# Sheet2.net
KiCad netlist of a schematic drawn in Altium Designer
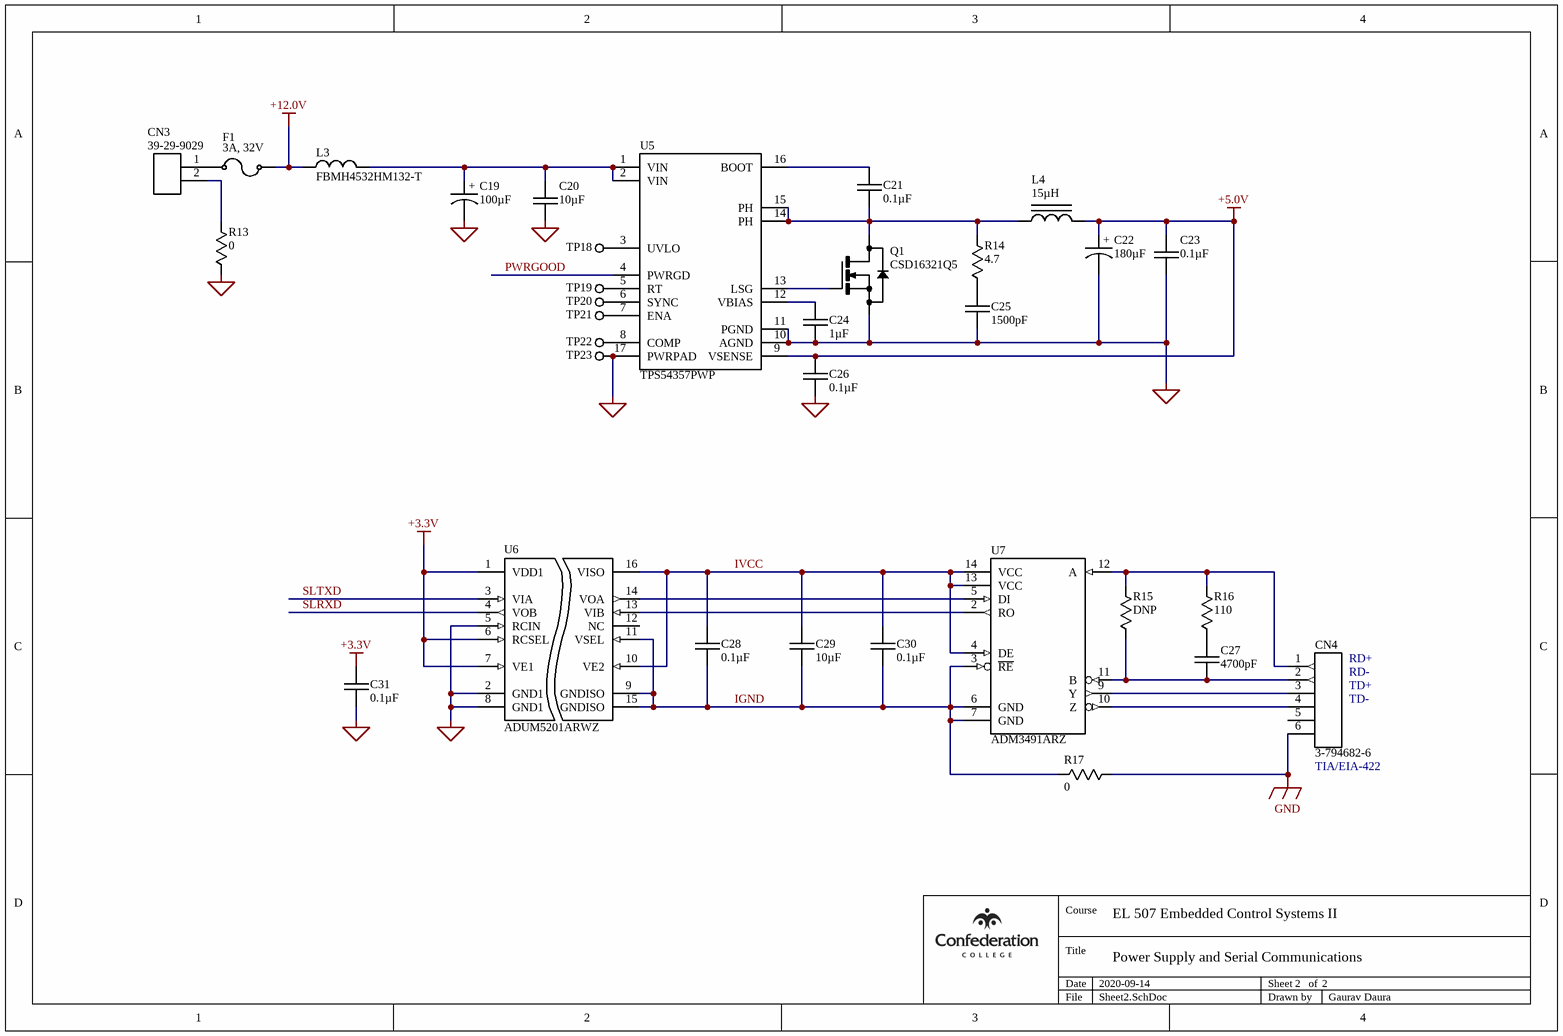
[diagram p0: Sheet2.SchDoc]

(export (version "E")
  (design (tool "Eeschema 10.0.6"))
  (components
    (comp (ref "C19")
      (value "100µF")
      (footprint "CAPAE660X770N")
      (description "100µF/25V/20% Aluminum Electrolytic Capacitor")
      (fields
        (field (name "MANUFACTURER") "Panasonic Corporation of North America")
        (field (name "PARTNUMBER") "EEE-1EA101XP")
      )
      (libsource (lib "EL507-LAB001") (part "EEE-1EA101XP"))
    )
    (comp (ref "C20")
      (value "10µF")
      (footprint "CAPC3225X250N")
      (description "10µF/50V/20% Multilayer Ceramic Chip Capacitor")
      (fields (field (name "MANUFACTURER") "Taiyo Yuden") (field (name "PARTNUMBER") "UMK325C7106MM-T"))
      (libsource (lib "EL507-LAB001") (part "UMK325C7106MM-T"))
    )
    (comp (ref "C21")
      (value "0.1µF")
      (footprint "CAPC2012X125N")
      (description "0.1µF/50V/±10% X7R Ceramic Chip Capacitor")
      (fields
        (field (name "MANUFACTURER") "Murata Manufacturing Co., Ltd.")
        (field (name "PARTNUMBER") "GRM21BR71H104KA01L")
      )
      (libsource (lib "EL507-LAB001") (part "GRM21BR71H104KA01L"))
    )
    (comp (ref "C22")
      (value "180µF")
      (footprint "CAPMP7343X190N")
      (description "180µF/6.3V/20% Low ESR Polymer Aluminum Capacitor (SP-CAP)")
      (fields
        (field (name "MANUFACTURER") "Panasonic Corporation of North America")
        (field (name "PARTNUMBER") "EEF-SE0J181R")
      )
      (libsource (lib "EL507-LAB001") (part "EEF-SE0J181R"))
    )
    (comp (ref "C23")
      (value "0.1µF")
      (footprint "CAPC2012X125N")
      (description "0.1µF/50V/±10% X7R Ceramic Chip Capacitor")
      (fields
        (field (name "MANUFACTURER") "Murata Manufacturing Co., Ltd.")
        (field (name "PARTNUMBER") "GRM21BR71H104KA01L")
      )
      (libsource (lib "EL507-LAB001") (part "GRM21BR71H104KA01L"))
    )
    (comp (ref "C24")
      (value "1µF")
      (footprint "CAPC2012X135N")
      (description "1µF/50V 10% X7R Multi-Layer Ceramic Capacitor")
      (fields
        (field (name "MANUFACTURER") "Samsung Electro-Mechanics")
        (field (name "PARTNUMBER") "CL21B105KBFNNNE")
      )
      (libsource (lib "EL507-LAB001") (part "CL21B105KBFNNNE"))
    )
    (comp (ref "C25")
      (value "1500pF")
      (footprint "CAPC2012X100N")
      (description "1500pF/250V/±10% X7R Ceramic Chip Capacitor")
      (fields
        (field (name "MANUFACTURER") "Murata Manufacturing Co., Ltd.")
        (field (name "PARTNUMBER") "GRM21AR72E152KW01D")
      )
      (libsource (lib "EL507-LAB001") (part "GRM21AR72E152KW01D"))
    )
    (comp (ref "C26")
      (value "0.1µF")
      (footprint "CAPC2012X125N")
      (description "0.1µF/50V/±10% X7R Ceramic Chip Capacitor")
      (fields
        (field (name "MANUFACTURER") "Murata Manufacturing Co., Ltd.")
        (field (name "PARTNUMBER") "GRM21BR71H104KA01L")
      )
      (libsource (lib "EL507-LAB001") (part "GRM21BR71H104KA01L"))
    )
    (comp (ref "C27")
      (value "4700pF")
      (footprint "CAPC2012X78N")
      (description "4700pF/50V/10% Ceramic Capacitor")
      (fields
        (field (name "MANUFACTURER") "Kemet Electronics Corporation")
        (field (name "PARTNUMBER") "C0805C472K5RACTU")
      )
      (libsource (lib "EL507-LAB001") (part "C0805C472K5RACTU"))
    )
    (comp (ref "C28")
      (value "0.1µF")
      (footprint "CAPC2012X125N")
      (description "0.1µF/50V/±10% X7R Ceramic Chip Capacitor")
      (fields
        (field (name "MANUFACTURER") "Murata Manufacturing Co., Ltd.")
        (field (name "PARTNUMBER") "GRM21BR71H104KA01L")
      )
      (libsource (lib "EL507-LAB001") (part "GRM21BR71H104KA01L"))
    )
    (comp (ref "C29")
      (value "10µF")
      (footprint "CAPC3225X250N")
      (description "10µF/50V/20% Multilayer Ceramic Chip Capacitor")
      (fields (field (name "MANUFACTURER") "Taiyo Yuden") (field (name "PARTNUMBER") "UMK325C7106MM-T"))
      (libsource (lib "EL507-LAB001") (part "UMK325C7106MM-T"))
    )
    (comp (ref "C30")
      (value "0.1µF")
      (footprint "CAPC2012X125N")
      (description "0.1µF/50V/±10% X7R Ceramic Chip Capacitor")
      (fields
        (field (name "MANUFACTURER") "Murata Manufacturing Co., Ltd.")
        (field (name "PARTNUMBER") "GRM21BR71H104KA01L")
      )
      (libsource (lib "EL507-LAB001") (part "GRM21BR71H104KA01L"))
    )
    (comp (ref "C31")
      (value "0.1µF")
      (footprint "CAPC2012X125N")
      (description "0.1µF/50V/±10% X7R Ceramic Chip Capacitor")
      (fields
        (field (name "MANUFACTURER") "Murata Manufacturing Co., Ltd.")
        (field (name "PARTNUMBER") "GRM21BR71H104KA01L")
      )
      (libsource (lib "EL507-LAB001") (part "GRM21BR71H104KA01L"))
    )
    (comp (ref "CN3")
      (value "39-29-9029")
      (footprint "MOLEX_39-29-9029")
      (fields (field (name "MANUFACTURER") "Molex Inc."))
      (libsource (lib "EL507-LAB001") (part "39-29-9029"))
    )
    (comp (ref "CN4")
      (value "3-794682-6")
      (footprint "TYCO_3-794682-6")
      (description "6 Circuit, Micro MATE-N-LOK 3 mm Vertical Connector")
      (fields (field (name "MANUFACTURER") "Tyco Electronics Corporation"))
      (libsource (lib "EL507-LAB001") (part "3-794682-6"))
    )
    (comp (ref "F1")
      (value "3A, 32V")
      (footprint "FUSE_0468XXX.NR")
      (description "1 A, 32 V, Slo-Blo, 468 Series Surface Mount Fuse")
      (fields (field (name "PARTNUMBER") "0468003.NR") (field (name "MANUFACTURER") "Littelfuse, Inc."))
      (libsource (lib "EL507-LAB001") (part "0468003.NR"))
    )
    (comp (ref "L3")
      (value "FBMH4532HM132-T")
      (footprint "INDC4532X350N")
      (description "Multilayer SMD Ferrite Bead, 3A, 1.3k @ 100 MHz")
      (fields (field (name "MANUFACTURER") "Taiyo Yuden"))
      (libsource (lib "EL507-LAB001") (part "FBMH4532HM132-T"))
    )
    (comp (ref "L4")
      (value "15µH")
      (footprint "IND_SRU1038-150Y")
      (description "15µH Shielded SMD Power Inductor")
      (fields (field (name "PARTNUMBER") "SRU1038-150Y") (field (name "MANUFACTURER") "Bourns, Inc."))
      (libsource (lib "EL507-LAB001") (part "SRU1038-150Y"))
    )
    (comp (ref "Q1")
      (value "CSD16321Q5")
      (footprint "TI_CSD16321Q5")
      (description "25V, 31 A, N-Channel Power MOSFET")
      (fields (field (name "MANUFACTURER") "Texas Instruments, Inc."))
      (libsource (lib "EL507-LAB001") (part "CSD16321Q5"))
    )
    (comp (ref "R13")
      (value "0")
      (footprint "RESC3216X60N")
      (description "0, 5%, 0.25W Thick Film Chip Resistor")
      (fields
        (field (name "MANUFACTURER") "Panasonic Corporation of North America")
        (field (name "PARTNUMBER") "ERJ-8GEY0R00V")
      )
      (libsource (lib "EL507-LAB001") (part "ERJ-8GEY0R00V"))
    )
    (comp (ref "R14")
      (value "4.7")
      (footprint "RESC2012X60N")
      (description "4.7, ±5%, 0.125W Thick Film Chip Resistor")
      (fields
        (field (name "MANUFACTURER") "Panasonic Corporation of North America")
        (field (name "PARTNUMBER") "ERJ-6GEYJ4R7V")
      )
      (libsource (lib "EL507-LAB001") (part "ERJ-6GEYJ4R7V"))
    )
    (comp (ref "R15")
      (value "DNP")
      (footprint "RESC2012X60N")
      (description "2012 Chip Resistor")
      (fields (field (name "MANUFACTURER") "Confederation College"))
      (libsource (lib "EL507-LAB001") (part "DNP_RESC2012X60N"))
    )
    (comp (ref "R16")
      (value "110")
      (footprint "RESC2012X60N")
      (description "110, 1%, 0.125W Precision Thick Film Chip Resistor")
      (fields
        (field (name "MANUFACTURER") "Panasonic Corporation of North America")
        (field (name "PARTNUMBER") "ERJ-6ENF1100V")
      )
      (libsource (lib "EL507-LAB001") (part "ERJ-6ENF1100V"))
    )
    (comp (ref "R17")
      (value "0")
      (footprint "RESC3216X60N")
      (description "0, 5%, 0.25W Thick Film Chip Resistor")
      (fields
        (field (name "MANUFACTURER") "Panasonic Corporation of North America")
        (field (name "PARTNUMBER") "ERJ-8GEY0R00V")
      )
      (libsource (lib "EL507-LAB001") (part "ERJ-8GEY0R00V"))
    )
    (comp (ref "TP18")
      (value "TESTPOINT100")
      (footprint "TP100")
      (description "Test Point")
      (fields (field (name "MANUFACTURER") "Confederation College"))
      (libsource (lib "EL507-LAB001") (part "TESTPOINT100"))
    )
    (comp (ref "TP19")
      (value "TESTPOINT100")
      (footprint "TP100")
      (description "Test Point")
      (fields (field (name "MANUFACTURER") "Confederation College"))
      (libsource (lib "EL507-LAB001") (part "TESTPOINT100"))
    )
    (comp (ref "TP20")
      (value "TESTPOINT100")
      (footprint "TP100")
      (description "Test Point")
      (fields (field (name "MANUFACTURER") "Confederation College"))
      (libsource (lib "EL507-LAB001") (part "TESTPOINT100"))
    )
    (comp (ref "TP21")
      (value "TESTPOINT100")
      (footprint "TP100")
      (description "Test Point")
      (fields (field (name "MANUFACTURER") "Confederation College"))
      (libsource (lib "EL507-LAB001") (part "TESTPOINT100"))
    )
    (comp (ref "TP22")
      (value "TESTPOINT100")
      (footprint "TP100")
      (description "Test Point")
      (fields (field (name "MANUFACTURER") "Confederation College"))
      (libsource (lib "EL507-LAB001") (part "TESTPOINT100"))
    )
    (comp (ref "TP23")
      (value "TESTPOINT100")
      (footprint "TP100")
      (description "Test Point")
      (fields (field (name "MANUFACTURER") "Confederation College"))
      (libsource (lib "EL507-LAB001") (part "TESTPOINT100"))
    )
    (comp (ref "U5")
      (value "TPS54357PWP")
      (footprint "SOP65P640X120-17AN")
      (description "5V, 4.5V to 20V Input, 3A Output Synchronous PWM Switcher with Integrated FET (SWIFT)")
      (fields (field (name "MANUFACTURER") "Texas Instruments, Inc."))
      (libsource (lib "EL507-LAB001") (part "TPS54357PWP"))
    )
    (comp (ref "U6")
      (value "ADUM5201ARWZ")
      (footprint "SOIC127P1030X265-16N")
      (description "1Mbps Dual Channel Digital Isolator with isoPower Integrated DC-to-DC Converter, 2.5 kV")
      (fields (field (name "MANUFACTURER") "Analog Devices, Inc."))
      (libsource (lib "EL507-LAB001") (part "ADUM5201ARWZ"))
    )
    (comp (ref "U7")
      (value "ADM3491ARZ")
      (footprint "SOIC127P600X175-14N")
      (description "3.3 V, Full Duplex, 840 uA, 20 Mbps, EIA RS-485 Transceiver")
      (fields (field (name "MANUFACTURER") "Analog Devices, Inc."))
      (libsource (lib "EL507-LAB001") (part "ADM3491ARZ"))
    )
  )
  (nets
    (net (code "1") (name "+3.3V") (class "Default")
      (node (ref "C31") (pin "1") (pinfunction "1_1") (pintype "passive"))
      (node (ref "U6") (pin "1") (pinfunction "VDD1_1") (pintype "power_in"))
      (node (ref "U6") (pin "6") (pinfunction "RCSEL_6") (pintype "input"))
      (node (ref "U6") (pin "7") (pinfunction "VE1_7") (pintype "input"))
    )
    (net (code "2") (name "+5.0V") (class "Default")
      (node (ref "C22") (pin "1") (pinfunction "1_1") (pintype "passive"))
      (node (ref "C23") (pin "1") (pinfunction "1_1") (pintype "passive"))
      (node (ref "C26") (pin "1") (pinfunction "1_1") (pintype "passive"))
      (node (ref "L4") (pin "2") (pinfunction "2_2") (pintype "passive"))
      (node (ref "U5") (pin "9") (pinfunction "VSENSE_9") (pintype "passive"))
    )
    (net (code "3") (name "+12.0V") (class "Default")
      (node (ref "F1") (pin "2") (pinfunction "2_2") (pintype "passive"))
      (node (ref "L3") (pin "1") (pinfunction "1_1") (pintype "passive"))
    )
    (net (code "4") (name "/IGND") (class "Default")
      (node (ref "C28") (pin "2") (pinfunction "2_2") (pintype "passive"))
      (node (ref "C29") (pin "2") (pinfunction "2_2") (pintype "passive"))
      (node (ref "C30") (pin "2") (pinfunction "2_2") (pintype "passive"))
      (node (ref "R17") (pin "1") (pinfunction "1_1") (pintype "passive"))
      (node (ref "U6") (pin "11") (pinfunction "VSEL_11") (pintype "input"))
      (node (ref "U6") (pin "15") (pinfunction "GNDISO_15") (pintype "power_in"))
      (node (ref "U6") (pin "9") (pinfunction "GNDISO_9") (pintype "power_in"))
      (node (ref "U7") (pin "3") (pinfunction "~{RE}_3") (pintype "input"))
      (node (ref "U7") (pin "6") (pinfunction "GND_6") (pintype "power_in"))
      (node (ref "U7") (pin "7") (pinfunction "GND_7") (pintype "power_in"))
    )
    (net (code "5") (name "/IVCC") (class "Default")
      (node (ref "C28") (pin "1") (pinfunction "1_1") (pintype "passive"))
      (node (ref "C29") (pin "1") (pinfunction "1_1") (pintype "passive"))
      (node (ref "C30") (pin "1") (pinfunction "1_1") (pintype "passive"))
      (node (ref "U6") (pin "10") (pinfunction "VE2_10") (pintype "input"))
      (node (ref "U6") (pin "16") (pinfunction "VISO_16") (pintype "power_in"))
      (node (ref "U7") (pin "13") (pinfunction "VCC_13") (pintype "power_in"))
      (node (ref "U7") (pin "14") (pinfunction "VCC_14") (pintype "power_in"))
      (node (ref "U7") (pin "4") (pinfunction "DE_4") (pintype "input"))
    )
    (net (code "6") (name "/PWRGOOD") (class "Default")
      (node (ref "U5") (pin "4") (pinfunction "PWRGD_4") (pintype "passive"))
    )
    (net (code "7") (name "/SLRXD") (class "Default")
      (node (ref "U6") (pin "4") (pinfunction "VOB_4") (pintype "output"))
    )
    (net (code "8") (name "/SLTXD") (class "Default")
      (node (ref "U6") (pin "3") (pinfunction "VIA_3") (pintype "input"))
    )
    (net (code "9") (name "GND") (class "Default")
      (node (ref "C19") (pin "2") (pinfunction "2_2") (pintype "passive"))
      (node (ref "C20") (pin "2") (pinfunction "2_2") (pintype "passive"))
      (node (ref "C22") (pin "2") (pinfunction "2_2") (pintype "passive"))
      (node (ref "C23") (pin "2") (pinfunction "2_2") (pintype "passive"))
      (node (ref "C24") (pin "2") (pinfunction "2_2") (pintype "passive"))
      (node (ref "C25") (pin "2") (pinfunction "2_2") (pintype "passive"))
      (node (ref "C26") (pin "2") (pinfunction "2_2") (pintype "passive"))
      (node (ref "C31") (pin "2") (pinfunction "2_2") (pintype "passive"))
      (node (ref "CN4") (pin "6") (pinfunction "6_6") (pintype "passive"))
      (node (ref "Q1") (pin "S") (pinfunction "S_S") (pintype "passive"))
      (node (ref "R13") (pin "1") (pinfunction "1_1") (pintype "passive"))
      (node (ref "R17") (pin "2") (pinfunction "2_2") (pintype "passive"))
      (node (ref "TP23") (pin "1") (pintype "passive"))
      (node (ref "U5") (pin "10") (pinfunction "AGND_10") (pintype "passive"))
      (node (ref "U5") (pin "11") (pinfunction "PGND_11") (pintype "passive"))
      (node (ref "U5") (pin "17") (pinfunction "PWRPAD_17") (pintype "power_in"))
      (node (ref "U6") (pin "2") (pinfunction "GND1_2") (pintype "power_in"))
      (node (ref "U6") (pin "5") (pinfunction "RCIN_5") (pintype "input"))
      (node (ref "U6") (pin "8") (pinfunction "GND1_8") (pintype "power_in"))
    )
    (net (code "10") (name "Net-(C19-Pad1)") (class "Default")
      (node (ref "C19") (pin "1") (pinfunction "1_1") (pintype "passive"))
      (node (ref "C20") (pin "1") (pinfunction "1_1") (pintype "passive"))
      (node (ref "L3") (pin "2") (pinfunction "2_2") (pintype "passive"))
      (node (ref "U5") (pin "1") (pinfunction "VIN_1") (pintype "passive"))
      (node (ref "U5") (pin "2") (pinfunction "VIN_2") (pintype "passive"))
    )
    (net (code "11") (name "Net-(C21-Pad2)") (class "Default")
      (node (ref "C21") (pin "2") (pinfunction "2_2") (pintype "passive"))
      (node (ref "L4") (pin "1") (pinfunction "1_1") (pintype "passive"))
      (node (ref "Q1") (pin "D") (pinfunction "D_D") (pintype "passive"))
      (node (ref "R14") (pin "2") (pinfunction "2_2") (pintype "passive"))
      (node (ref "U5") (pin "14") (pinfunction "PH_14") (pintype "passive"))
      (node (ref "U5") (pin "15") (pinfunction "PH_15") (pintype "passive"))
    )
    (net (code "12") (name "Net-(C25-Pad1)") (class "Default")
      (node (ref "C25") (pin "1") (pinfunction "1_1") (pintype "passive"))
      (node (ref "R14") (pin "1") (pinfunction "1_1") (pintype "passive"))
    )
    (net (code "13") (name "Net-(C27-Pad1)") (class "Default")
      (node (ref "C27") (pin "1") (pinfunction "1_1") (pintype "passive"))
      (node (ref "R16") (pin "1") (pinfunction "1_1") (pintype "passive"))
    )
    (net (code "14") (name "Net-(CN3-Pad1)") (class "Default")
      (node (ref "CN3") (pin "1") (pintype "passive"))
      (node (ref "F1") (pin "1") (pinfunction "1_1") (pintype "passive"))
    )
    (net (code "15") (name "Net-(CN3-Pad2)") (class "Default")
      (node (ref "CN3") (pin "2") (pintype "passive"))
      (node (ref "R13") (pin "2") (pinfunction "2_2") (pintype "passive"))
    )
    (net (code "16") (name "Net-(U5-BOOT)") (class "Default")
      (node (ref "C21") (pin "1") (pinfunction "1_1") (pintype "passive"))
      (node (ref "U5") (pin "16") (pinfunction "BOOT_16") (pintype "passive"))
    )
    (net (code "17") (name "Net-(U5-COMP)") (class "Default")
      (node (ref "TP22") (pin "1") (pintype "passive"))
      (node (ref "U5") (pin "8") (pinfunction "COMP_8") (pintype "passive"))
    )
    (net (code "18") (name "Net-(U5-ENA)") (class "Default")
      (node (ref "TP21") (pin "1") (pintype "passive"))
      (node (ref "U5") (pin "7") (pinfunction "ENA_7") (pintype "passive"))
    )
    (net (code "19") (name "Net-(U5-LSG)") (class "Default")
      (node (ref "Q1") (pin "G") (pinfunction "G_G") (pintype "passive"))
      (node (ref "U5") (pin "13") (pinfunction "LSG_13") (pintype "passive"))
    )
    (net (code "20") (name "Net-(U5-RT)") (class "Default")
      (node (ref "TP19") (pin "1") (pintype "passive"))
      (node (ref "U5") (pin "5") (pinfunction "RT_5") (pintype "passive"))
    )
    (net (code "21") (name "Net-(U5-SYNC)") (class "Default")
      (node (ref "TP20") (pin "1") (pintype "passive"))
      (node (ref "U5") (pin "6") (pinfunction "SYNC_6") (pintype "passive"))
    )
    (net (code "22") (name "Net-(U5-UVLO)") (class "Default")
      (node (ref "TP18") (pin "1") (pintype "passive"))
      (node (ref "U5") (pin "3") (pinfunction "UVLO_3") (pintype "passive"))
    )
    (net (code "23") (name "Net-(U5-VBIAS)") (class "Default")
      (node (ref "C24") (pin "1") (pinfunction "1_1") (pintype "passive"))
      (node (ref "U5") (pin "12") (pinfunction "VBIAS_12") (pintype "passive"))
    )
    (net (code "24") (name "Net-(U6-VIB)") (class "Default")
      (node (ref "U6") (pin "13") (pinfunction "VIB_13") (pintype "input"))
      (node (ref "U7") (pin "2") (pinfunction "RO_2") (pintype "output"))
    )
    (net (code "25") (name "Net-(U6-VOA)") (class "Default")
      (node (ref "U6") (pin "14") (pinfunction "VOA_14") (pintype "output"))
      (node (ref "U7") (pin "5") (pinfunction "DI_5") (pintype "input"))
    )
    (net (code "26") (name "Net-(U7-A)") (class "Default")
      (node (ref "CN4") (pin "1") (pinfunction "1_1") (pintype "output"))
      (node (ref "R15") (pin "2") (pinfunction "2_2") (pintype "passive"))
      (node (ref "R16") (pin "2") (pinfunction "2_2") (pintype "passive"))
      (node (ref "U7") (pin "12") (pinfunction "A_12") (pintype "input"))
    )
    (net (code "27") (name "Net-(U7-B)") (class "Default")
      (node (ref "C27") (pin "2") (pinfunction "2_2") (pintype "passive"))
      (node (ref "CN4") (pin "2") (pinfunction "2_2") (pintype "output"))
      (node (ref "R15") (pin "1") (pinfunction "1_1") (pintype "passive"))
      (node (ref "U7") (pin "11") (pinfunction "B_11") (pintype "input"))
    )
    (net (code "28") (name "Net-(U7-Y)") (class "Default")
      (node (ref "CN4") (pin "3") (pinfunction "3_3") (pintype "passive"))
      (node (ref "U7") (pin "9") (pinfunction "Y_9") (pintype "output"))
    )
    (net (code "29") (name "Net-(U7-Z)") (class "Default")
      (node (ref "CN4") (pin "4") (pinfunction "4_4") (pintype "passive"))
      (node (ref "U7") (pin "10") (pinfunction "Z_10") (pintype "output"))
    )
    (net (code "30") (name "unconnected-(CN4-Pad5)") (class "Default")
      (node (ref "CN4") (pin "5") (pinfunction "5_5") (pintype "passive"))
    )
    (net (code "31") (name "unconnected-(U6-NC-Pad12)") (class "Default")
      (node (ref "U6") (pin "12") (pinfunction "NC_12") (pintype "passive"))
    )
  )
)
